# Boost_converter.net
KiCad netlist of a schematic drawn in Altium Designer
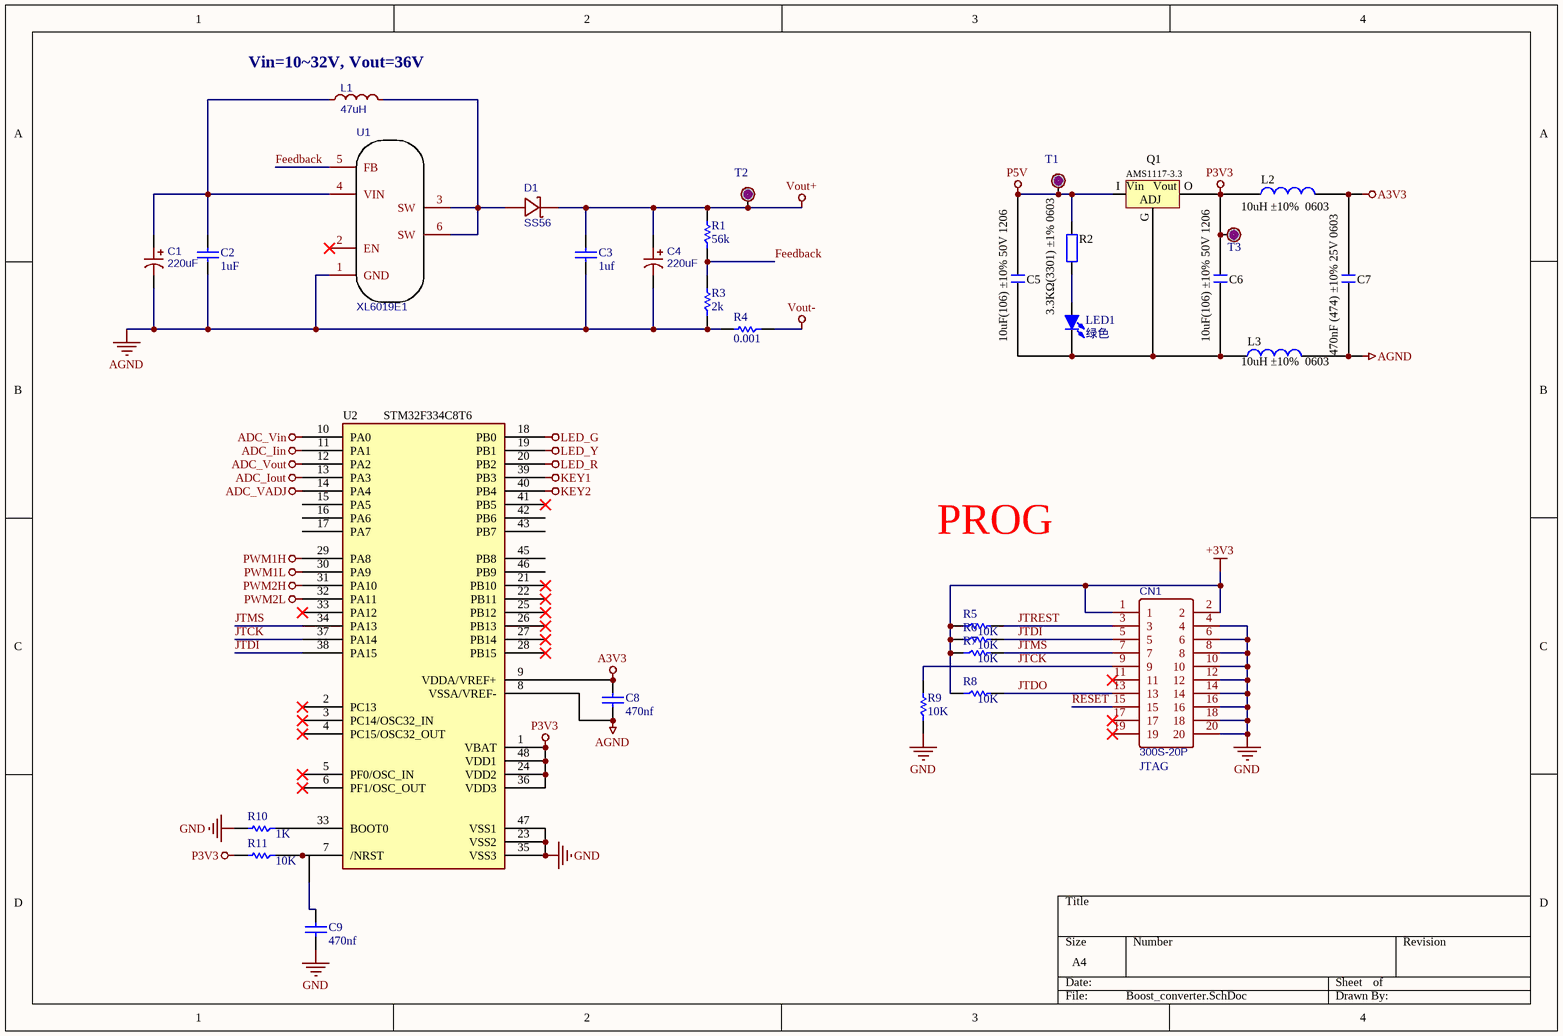
[diagram p0: Boost_converter.SchDoc]

(export (version "E")
  (design (tool "Eeschema 10.0.6"))
  (components
    (comp (ref "C1")
      (value "220uF")
      (footprint "CAP-SMD_BD10.0-L10.3-W10.3-LS11.0-FD")
      (fields
        (field (name "BOM_SUPPLIER PART") "C2887271")
        (field (name "BOM_MANUFACTURER PART") "RVT220UF50V67RV0021")
        (field (name "CONTRIBUTOR") "LCSC")
      )
      (libsource (lib "Portable power supply") (part "220uF"))
    )
    (comp (ref "C2")
      (value "1uF")
      (footprint "0805C")
      (description "Capacitor")
      (fields (field (name "REVIEWED BY") "RM - 2018/08/05"))
      (libsource (lib "Portable power supply") (part "C_1uf"))
    )
    (comp (ref "C3")
      (value "1uf")
      (footprint "C0805_L")
      (description "贴片电容/MLCC电容")
      (libsource (lib "0.1 - 电阻-电容-电感-晶振-晶体-磁珠-电位器-法拉电容-馈通电容") (part "C"))
    )
    (comp (ref "C4")
      (value "220uF")
      (footprint "CAP-SMD_BD10.0-L10.3-W10.3-LS11.0-FD")
      (fields
        (field (name "BOM_SUPPLIER PART") "C2887271")
        (field (name "BOM_MANUFACTURER PART") "RVT220UF50V67RV0021")
        (field (name "CONTRIBUTOR") "LCSC")
      )
      (libsource (lib "Portable power supply") (part "220uF"))
    )
    (comp (ref "C5")
      (value "10uF(106) ±10% 50V 1206")
      (footprint "C 1206_M")
      (description "贴片电容")
      (libsource (lib "0.1 - 电阻-电容-电感") (part "C"))
    )
    (comp (ref "C6")
      (value "10uF(106) ±10% 50V 1206")
      (footprint "C 1206_M")
      (description "贴片电容")
      (libsource (lib "0.1 - 电阻-电容-电感") (part "C"))
    )
    (comp (ref "C7")
      (value "470nF (474) ±10% 25V 0603")
      (footprint "C 0603_L")
      (description "贴片电容")
      (libsource (lib "0.1 - 电阻-电容-电感") (part "C"))
    )
    (comp (ref "C8")
      (value "470nf")
      (footprint "0805C")
      (description "Capacitor")
      (fields (field (name "REVIEWED BY") "RM - 2018/08/05"))
      (libsource (lib "Portable power supply") (part "C_330uf"))
    )
    (comp (ref "C9")
      (value "470nf")
      (footprint "0805C")
      (description "Capacitor")
      (fields (field (name "REVIEWED BY") "RM - 2018/08/05"))
      (libsource (lib "Portable power supply") (part "C_330uf"))
    )
    (comp (ref "CN1")
      (value "300S-20P")
      (footprint "CONN-TH_300S-20P")
      (fields (field (name "BOM_SUPPLIER PART") "C132442") (field (name "CONTRIBUTOR") "LCSC"))
      (libsource (lib "Portable power supply") (part "300S-20P"))
    )
    (comp (ref "D1")
      (value "SS56")
      (footprint "SMA_L4.3-W2.6-LS5.2-RD")
      (fields (field (name "BOM_SUPPLIER PART") "C65009"))
      (libsource (lib "Portable power supply") (part "SS56"))
    )
    (comp (ref "L1")
      (value "47uH")
      (footprint "IND-SMD_L12.6-W12.6_MCF-13XX")
      (fields
        (field (name "BOM_SUPPLIER PART") "C497913")
        (field (name "BOM_MANUFACTURER PART") "YSPI1365-470M")
        (field (name "CONTRIBUTOR") "LCSC")
      )
      (libsource (lib "Portable power supply") (part "47uH"))
    )
    (comp (ref "L2")
      (value "10uH ±10%  0603")
      (footprint "L 0603")
      (description "小功率贴片电感")
      (libsource (lib "0.1 - 电阻-电容-电感") (part "L"))
    )
    (comp (ref "L3")
      (value "10uH ±10%  0603")
      (footprint "L 0603")
      (description "小功率贴片电感")
      (libsource (lib "0.1 - 电阻-电容-电感") (part "L"))
    )
    (comp (ref "LED1")
      (value "绿色")
      (footprint "LED 0603R")
      (description "贴片LED")
      (fields (field (name "版权归属") "封装库来自淘宝 ID：黄晶宝石"))
      (libsource (lib "0.3 - LED发光二极管") (part "LED-SMD"))
    )
    (comp (ref "Q1")
      (value "AMS1117-3.3")
      (footprint "SOT-223")
      (libsource (lib "PFC control board") (part "NCP1117ST50T3G"))
    )
    (comp (ref "R1")
      (value "56k")
      (footprint "0805")
      (description "Resistor")
      (fields (field (name "REVIEWED BY") "RM - 2018/08/05"))
      (libsource (lib "Portable power supply") (part "R_12k"))
    )
    (comp (ref "R2")
      (value "3.3KΩ(3301) ±1% 0603")
      (footprint "R 0603_L")
      (description "贴片电阻")
      (fields (field (name "版权归属") "来自淘宝 ID：黄晶宝石"))
      (libsource (lib "0.1 - 电阻-电容-电感") (part "R"))
    )
    (comp (ref "R3")
      (value "2k")
      (footprint "0805")
      (description "Resistor")
      (fields (field (name "REVIEWED BY") "RM - 2018/08/05"))
      (libsource (lib "Portable power supply") (part "R_2k"))
    )
    (comp (ref "R4")
      (value "0.001")
      (footprint "0805")
      (description "Resistor")
      (fields (field (name "REVIEWED BY") "RM - 2018/08/05"))
      (libsource (lib "Portable power supply") (part "R_12k"))
    )
    (comp (ref "R5")
      (value "10K")
      (footprint "0805")
      (description "Resistor")
      (fields (field (name "REVIEWED BY") "RM - 2018/08/05"))
      (libsource (lib "Portable power supply") (part "R_10k"))
    )
    (comp (ref "R6")
      (value "10K")
      (footprint "0805")
      (description "Resistor")
      (fields (field (name "REVIEWED BY") "RM - 2018/08/05"))
      (libsource (lib "Portable power supply") (part "R_10k"))
    )
    (comp (ref "R7")
      (value "10K")
      (footprint "0805")
      (description "Resistor")
      (fields (field (name "REVIEWED BY") "RM - 2018/08/05"))
      (libsource (lib "Portable power supply") (part "R_10k"))
    )
    (comp (ref "R8")
      (value "10K")
      (footprint "0805")
      (description "Resistor")
      (fields (field (name "REVIEWED BY") "RM - 2018/08/05"))
      (libsource (lib "Portable power supply") (part "R_10k"))
    )
    (comp (ref "R9")
      (value "10K")
      (footprint "0805")
      (description "Resistor")
      (fields (field (name "REVIEWED BY") "RM - 2018/08/05"))
      (libsource (lib "Portable power supply") (part "R_10k"))
    )
    (comp (ref "R10")
      (value "1K")
      (footprint "0805")
      (description "Resistor")
      (fields (field (name "REVIEWED BY") "RM - 2018/08/05"))
      (libsource (lib "Portable power supply") (part "R_1k"))
    )
    (comp (ref "R11")
      (value "10K")
      (footprint "0805")
      (description "Resistor")
      (fields (field (name "REVIEWED BY") "RM - 2018/08/05"))
      (libsource (lib "Portable power supply") (part "R_1k"))
    )
    (comp (ref "T1") (value "TestP") (footprint "TestP") (libsource (lib "CSS02404A") (part "TestP")))
    (comp (ref "T2") (value "TestP") (footprint "TestP") (libsource (lib "CSS02404A") (part "TestP")))
    (comp (ref "T3") (value "TestP") (footprint "TestP") (libsource (lib "CSS02404A") (part "TestP")))
    (comp (ref "U1")
      (value "XL6019E1")
      (footprint "TO-263-5_L10.2-W9.9-P1.70-LS14.4-TL")
      (fields (field (name "BOM_SUPPLIER PART") "C73018"))
      (libsource (lib "Portable power supply") (part "XL6019E1"))
    )
    (comp (ref "U2")
      (value "STM32F334C8T6")
      (footprint "CBB024D-1-V1.2:LQFP48-7*7")
      (libsource (lib "CBB012DV-V1.0") (part "STM32F334C8T6"))
    )
  )
  (nets
    (net (code "1") (name "+3V3") (class "Default")
      (node (ref "CN1") (pin "1") (pinfunction "1_1") (pintype "passive"))
      (node (ref "CN1") (pin "2") (pinfunction "2_2") (pintype "passive"))
      (node (ref "R5") (pin "1") (pintype "passive"))
      (node (ref "R6") (pin "1") (pintype "passive"))
      (node (ref "R7") (pin "1") (pintype "passive"))
      (node (ref "R8") (pin "1") (pintype "passive"))
    )
    (net (code "2") (name "/Feedback") (class "Default")
      (node (ref "R1") (pin "1") (pintype "passive"))
      (node (ref "R3") (pin "2") (pintype "passive"))
      (node (ref "U1") (pin "5") (pinfunction "FB_5") (pintype "passive"))
    )
    (net (code "3") (name "/JTCK") (class "Default")
      (node (ref "CN1") (pin "9") (pinfunction "9_9") (pintype "passive"))
      (node (ref "R9") (pin "2") (pintype "passive"))
      (node (ref "U2") (pin "37") (pinfunction "PA14_37") (pintype "passive"))
    )
    (net (code "4") (name "/JTDI") (class "Default")
      (node (ref "CN1") (pin "5") (pinfunction "5_5") (pintype "passive"))
      (node (ref "R6") (pin "2") (pintype "passive"))
      (node (ref "U2") (pin "38") (pinfunction "PA15_38") (pintype "passive"))
    )
    (net (code "5") (name "/JTDO") (class "Default")
      (node (ref "CN1") (pin "13") (pinfunction "13_13") (pintype "passive"))
      (node (ref "R8") (pin "2") (pintype "passive"))
    )
    (net (code "6") (name "/JTMS") (class "Default")
      (node (ref "CN1") (pin "7") (pinfunction "7_7") (pintype "passive"))
      (node (ref "R7") (pin "2") (pintype "passive"))
      (node (ref "U2") (pin "34") (pinfunction "PA13_34") (pintype "passive"))
    )
    (net (code "7") (name "/JTREST") (class "Default")
      (node (ref "CN1") (pin "3") (pinfunction "3_3") (pintype "passive"))
      (node (ref "R5") (pin "2") (pintype "passive"))
    )
    (net (code "8") (name "/RESET") (class "Default")
      (node (ref "CN1") (pin "15") (pinfunction "15_15") (pintype "passive"))
    )
    (net (code "9") (name "A3V3") (class "Default")
      (node (ref "C7") (pin "1") (pinfunction "1_1") (pintype "passive"))
      (node (ref "C8") (pin "1") (pinfunction "1_1") (pintype "passive"))
      (node (ref "L2") (pin "2") (pinfunction "2_2") (pintype "passive"))
      (node (ref "U2") (pin "9") (pinfunction "VDDA/VREF+_9") (pintype "passive"))
    )
    (net (code "10") (name "ADC_Iin") (class "Default")
      (node (ref "U2") (pin "11") (pinfunction "PA1_11") (pintype "passive"))
    )
    (net (code "11") (name "ADC_Iout") (class "Default")
      (node (ref "U2") (pin "13") (pinfunction "PA3_13") (pintype "passive"))
    )
    (net (code "12") (name "ADC_VADJ") (class "Default")
      (node (ref "U2") (pin "14") (pinfunction "PA4_14") (pintype "passive"))
    )
    (net (code "13") (name "ADC_Vin") (class "Default")
      (node (ref "U2") (pin "10") (pinfunction "PA0_10") (pintype "passive"))
    )
    (net (code "14") (name "ADC_Vout") (class "Default")
      (node (ref "U2") (pin "12") (pinfunction "PA2_12") (pintype "passive"))
    )
    (net (code "15") (name "AGND") (class "Default")
      (node (ref "C1") (pin "2") (pinfunction "2_2") (pintype "passive"))
      (node (ref "C2") (pin "2") (pinfunction "2_2") (pintype "passive"))
      (node (ref "C3") (pin "1") (pinfunction "1_1") (pintype "passive"))
      (node (ref "C4") (pin "2") (pinfunction "2_2") (pintype "passive"))
      (node (ref "C7") (pin "2") (pinfunction "2_2") (pintype "passive"))
      (node (ref "C8") (pin "2") (pinfunction "2_2") (pintype "passive"))
      (node (ref "L3") (pin "2") (pinfunction "2_2") (pintype "passive"))
      (node (ref "R3") (pin "1") (pintype "passive"))
      (node (ref "R4") (pin "2") (pintype "passive"))
      (node (ref "U1") (pin "1") (pinfunction "GND_1") (pintype "passive"))
      (node (ref "U2") (pin "8") (pinfunction "VSSA/VREF-_8") (pintype "passive"))
    )
    (net (code "16") (name "GND") (class "Default")
      (node (ref "C9") (pin "2") (pinfunction "2_2") (pintype "passive"))
      (node (ref "CN1") (pin "10") (pinfunction "10_10") (pintype "passive"))
      (node (ref "CN1") (pin "12") (pinfunction "12_12") (pintype "passive"))
      (node (ref "CN1") (pin "14") (pinfunction "14_14") (pintype "passive"))
      (node (ref "CN1") (pin "16") (pinfunction "16_16") (pintype "passive"))
      (node (ref "CN1") (pin "18") (pinfunction "18_18") (pintype "passive"))
      (node (ref "CN1") (pin "20") (pinfunction "20_20") (pintype "passive"))
      (node (ref "CN1") (pin "4") (pinfunction "4_4") (pintype "passive"))
      (node (ref "CN1") (pin "6") (pinfunction "6_6") (pintype "passive"))
      (node (ref "CN1") (pin "8") (pinfunction "8_8") (pintype "passive"))
      (node (ref "R10") (pin "2") (pintype "passive"))
      (node (ref "R9") (pin "1") (pintype "passive"))
      (node (ref "U2") (pin "23") (pinfunction "VSS2_23") (pintype "passive"))
      (node (ref "U2") (pin "35") (pinfunction "VSS3_35") (pintype "passive"))
      (node (ref "U2") (pin "47") (pinfunction "VSS1_47") (pintype "passive"))
    )
    (net (code "17") (name "KEY1") (class "Default")
      (node (ref "U2") (pin "39") (pinfunction "PB3_39") (pintype "passive"))
    )
    (net (code "18") (name "KEY2") (class "Default")
      (node (ref "U2") (pin "40") (pinfunction "PB4_40") (pintype "passive"))
    )
    (net (code "19") (name "LED_G") (class "Default")
      (node (ref "U2") (pin "18") (pinfunction "PB0_18") (pintype "passive"))
    )
    (net (code "20") (name "LED_R") (class "Default")
      (node (ref "U2") (pin "20") (pinfunction "PB2_20") (pintype "passive"))
    )
    (net (code "21") (name "LED_Y") (class "Default")
      (node (ref "U2") (pin "19") (pinfunction "PB1_19") (pintype "passive"))
    )
    (net (code "22") (name "Net-(D1-A)") (class "Default")
      (node (ref "D1") (pin "2") (pinfunction "A_2") (pintype "passive"))
      (node (ref "L1") (pin "2") (pinfunction "2_2") (pintype "passive"))
      (node (ref "U1") (pin "3") (pinfunction "SW_3") (pintype "passive"))
      (node (ref "U1") (pin "6") (pinfunction "SW_6") (pintype "passive"))
    )
    (net (code "23") (name "Net-(LED1-A)") (class "Default")
      (node (ref "LED1") (pin "1") (pinfunction "A_1") (pintype "passive"))
      (node (ref "R2") (pin "2") (pinfunction "2_2") (pintype "passive"))
    )
    (net (code "24") (name "Net-(LED1-K)") (class "Default")
      (node (ref "C5") (pin "1") (pinfunction "1_1") (pintype "passive"))
      (node (ref "C6") (pin "1") (pinfunction "1_1") (pintype "passive"))
      (node (ref "L3") (pin "1") (pinfunction "1_1") (pintype "passive"))
      (node (ref "LED1") (pin "2") (pinfunction "K_2") (pintype "passive"))
      (node (ref "Q1") (pin "G") (pinfunction "G_G") (pintype "passive"))
    )
    (net (code "25") (name "Net-(U1-VIN)") (class "Default")
      (node (ref "C1") (pin "1") (pinfunction "1_1") (pintype "passive"))
      (node (ref "C2") (pin "1") (pinfunction "1_1") (pintype "passive"))
      (node (ref "L1") (pin "1") (pinfunction "1_1") (pintype "passive"))
      (node (ref "U1") (pin "4") (pinfunction "VIN_4") (pintype "passive"))
    )
    (net (code "26") (name "Net-(U2-BOOT0)") (class "Default")
      (node (ref "R10") (pin "1") (pintype "passive"))
      (node (ref "U2") (pin "33") (pinfunction "BOOT0_33") (pintype "passive"))
    )
    (net (code "27") (name "Net-(U2-{slash}NRST)") (class "Default")
      (node (ref "C9") (pin "1") (pinfunction "1_1") (pintype "passive"))
      (node (ref "R11") (pin "1") (pintype "passive"))
      (node (ref "U2") (pin "7") (pinfunction "/NRST_7") (pintype "passive"))
    )
    (net (code "28") (name "P3V3") (class "Default")
      (node (ref "C6") (pin "2") (pinfunction "2_2") (pintype "passive"))
      (node (ref "L2") (pin "1") (pinfunction "1_1") (pintype "passive"))
      (node (ref "Q1") (pin "O") (pinfunction "OUT_O") (pintype "passive"))
      (node (ref "R11") (pin "2") (pintype "passive"))
      (node (ref "T3") (pin "0") (pinfunction "0_0") (pintype "passive"))
      (node (ref "U2") (pin "1") (pinfunction "VBAT_1") (pintype "passive"))
      (node (ref "U2") (pin "24") (pinfunction "VDD2_24") (pintype "passive"))
      (node (ref "U2") (pin "36") (pinfunction "VDD3_36") (pintype "passive"))
      (node (ref "U2") (pin "48") (pinfunction "VDD1_48") (pintype "passive"))
    )
    (net (code "29") (name "P5V") (class "Default")
      (node (ref "C5") (pin "2") (pinfunction "2_2") (pintype "passive"))
      (node (ref "Q1") (pin "I") (pinfunction "IN_I") (pintype "passive"))
      (node (ref "R2") (pin "1") (pinfunction "1_1") (pintype "passive"))
      (node (ref "T1") (pin "0") (pinfunction "0_0") (pintype "passive"))
    )
    (net (code "30") (name "PWM1H") (class "Default")
      (node (ref "U2") (pin "29") (pinfunction "PA8_29") (pintype "passive"))
    )
    (net (code "31") (name "PWM1L") (class "Default")
      (node (ref "U2") (pin "30") (pinfunction "PA9_30") (pintype "passive"))
    )
    (net (code "32") (name "PWM2H") (class "Default")
      (node (ref "U2") (pin "31") (pinfunction "PA10_31") (pintype "passive"))
    )
    (net (code "33") (name "PWM2L") (class "Default")
      (node (ref "U2") (pin "32") (pinfunction "PA11_32") (pintype "passive"))
    )
    (net (code "34") (name "Vout+") (class "Default")
      (node (ref "C3") (pin "2") (pinfunction "2_2") (pintype "passive"))
      (node (ref "C4") (pin "1") (pinfunction "1_1") (pintype "passive"))
      (node (ref "D1") (pin "1") (pinfunction "K_1") (pintype "passive"))
      (node (ref "R1") (pin "2") (pintype "passive"))
      (node (ref "T2") (pin "0") (pinfunction "0_0") (pintype "passive"))
    )
    (net (code "35") (name "Vout-") (class "Default") (node (ref "R4") (pin "1") (pintype "passive")))
    (net (code "36") (name "unconnected-(CN1-Pad11)") (class "Default")
      (node (ref "CN1") (pin "11") (pinfunction "11_11") (pintype "passive+no_connect"))
    )
    (net (code "37") (name "unconnected-(CN1-Pad17)") (class "Default")
      (node (ref "CN1") (pin "17") (pinfunction "17_17") (pintype "passive+no_connect"))
    )
    (net (code "38") (name "unconnected-(CN1-Pad19)") (class "Default")
      (node (ref "CN1") (pin "19") (pinfunction "19_19") (pintype "passive+no_connect"))
    )
    (net (code "39") (name "unconnected-(U1-EN-Pad2)") (class "Default")
      (node (ref "U1") (pin "2") (pinfunction "EN_2") (pintype "passive+no_connect"))
    )
    (net (code "40") (name "unconnected-(U2-PA5-Pad15)") (class "Default")
      (node (ref "U2") (pin "15") (pinfunction "PA5_15") (pintype "passive"))
    )
    (net (code "41") (name "unconnected-(U2-PA6-Pad16)") (class "Default")
      (node (ref "U2") (pin "16") (pinfunction "PA6_16") (pintype "passive"))
    )
    (net (code "42") (name "unconnected-(U2-PA7-Pad17)") (class "Default")
      (node (ref "U2") (pin "17") (pinfunction "PA7_17") (pintype "passive"))
    )
    (net (code "43") (name "unconnected-(U2-PA12-Pad33)") (class "Default")
      (node (ref "U2") (pin "33") (pinfunction "PA12_33") (pintype "passive+no_connect"))
    )
    (net (code "44") (name "unconnected-(U2-PB5-Pad41)") (class "Default")
      (node (ref "U2") (pin "41") (pinfunction "PB5_41") (pintype "passive+no_connect"))
    )
    (net (code "45") (name "unconnected-(U2-PB6-Pad42)") (class "Default")
      (node (ref "U2") (pin "42") (pinfunction "PB6_42") (pintype "passive"))
    )
    (net (code "46") (name "unconnected-(U2-PB7-Pad43)") (class "Default")
      (node (ref "U2") (pin "43") (pinfunction "PB7_43") (pintype "passive"))
    )
    (net (code "47") (name "unconnected-(U2-PB8-Pad45)") (class "Default")
      (node (ref "U2") (pin "45") (pinfunction "PB8_45") (pintype "passive"))
    )
    (net (code "48") (name "unconnected-(U2-PB9-Pad46)") (class "Default")
      (node (ref "U2") (pin "46") (pinfunction "PB9_46") (pintype "passive"))
    )
    (net (code "49") (name "unconnected-(U2-PB10-Pad21)") (class "Default")
      (node (ref "U2") (pin "21") (pinfunction "PB10_21") (pintype "passive+no_connect"))
    )
    (net (code "50") (name "unconnected-(U2-PB11-Pad22)") (class "Default")
      (node (ref "U2") (pin "22") (pinfunction "PB11_22") (pintype "passive+no_connect"))
    )
    (net (code "51") (name "unconnected-(U2-PB12-Pad25)") (class "Default")
      (node (ref "U2") (pin "25") (pinfunction "PB12_25") (pintype "passive+no_connect"))
    )
    (net (code "52") (name "unconnected-(U2-PB13-Pad26)") (class "Default")
      (node (ref "U2") (pin "26") (pinfunction "PB13_26") (pintype "passive+no_connect"))
    )
    (net (code "53") (name "unconnected-(U2-PB14-Pad27)") (class "Default")
      (node (ref "U2") (pin "27") (pinfunction "PB14_27") (pintype "passive+no_connect"))
    )
    (net (code "54") (name "unconnected-(U2-PB15-Pad28)") (class "Default")
      (node (ref "U2") (pin "28") (pinfunction "PB15_28") (pintype "passive+no_connect"))
    )
    (net (code "55") (name "unconnected-(U2-PC13-Pad2)") (class "Default")
      (node (ref "U2") (pin "2") (pinfunction "PC13_2") (pintype "passive+no_connect"))
    )
    (net (code "56") (name "unconnected-(U2-PC14{slash}OSC32_IN-Pad3)") (class "Default")
      (node (ref "U2") (pin "3") (pinfunction "PC14/OSC32_IN_3") (pintype "passive+no_connect"))
    )
    (net (code "57") (name "unconnected-(U2-PC15{slash}OSC32_OUT-Pad4)") (class "Default")
      (node (ref "U2") (pin "4") (pinfunction "PC15/OSC32_OUT_4") (pintype "passive+no_connect"))
    )
    (net (code "58") (name "unconnected-(U2-PF0{slash}OSC_IN-Pad5)") (class "Default")
      (node (ref "U2") (pin "5") (pinfunction "PF0/OSC_IN_5") (pintype "passive+no_connect"))
    )
    (net (code "59") (name "unconnected-(U2-PF1{slash}OSC_OUT-Pad6)") (class "Default")
      (node (ref "U2") (pin "6") (pinfunction "PF1/OSC_OUT_6") (pintype "passive+no_connect"))
    )
  )
)
